# Output_Transceivers.net
KiCad netlist of a schematic drawn in Altium Designer
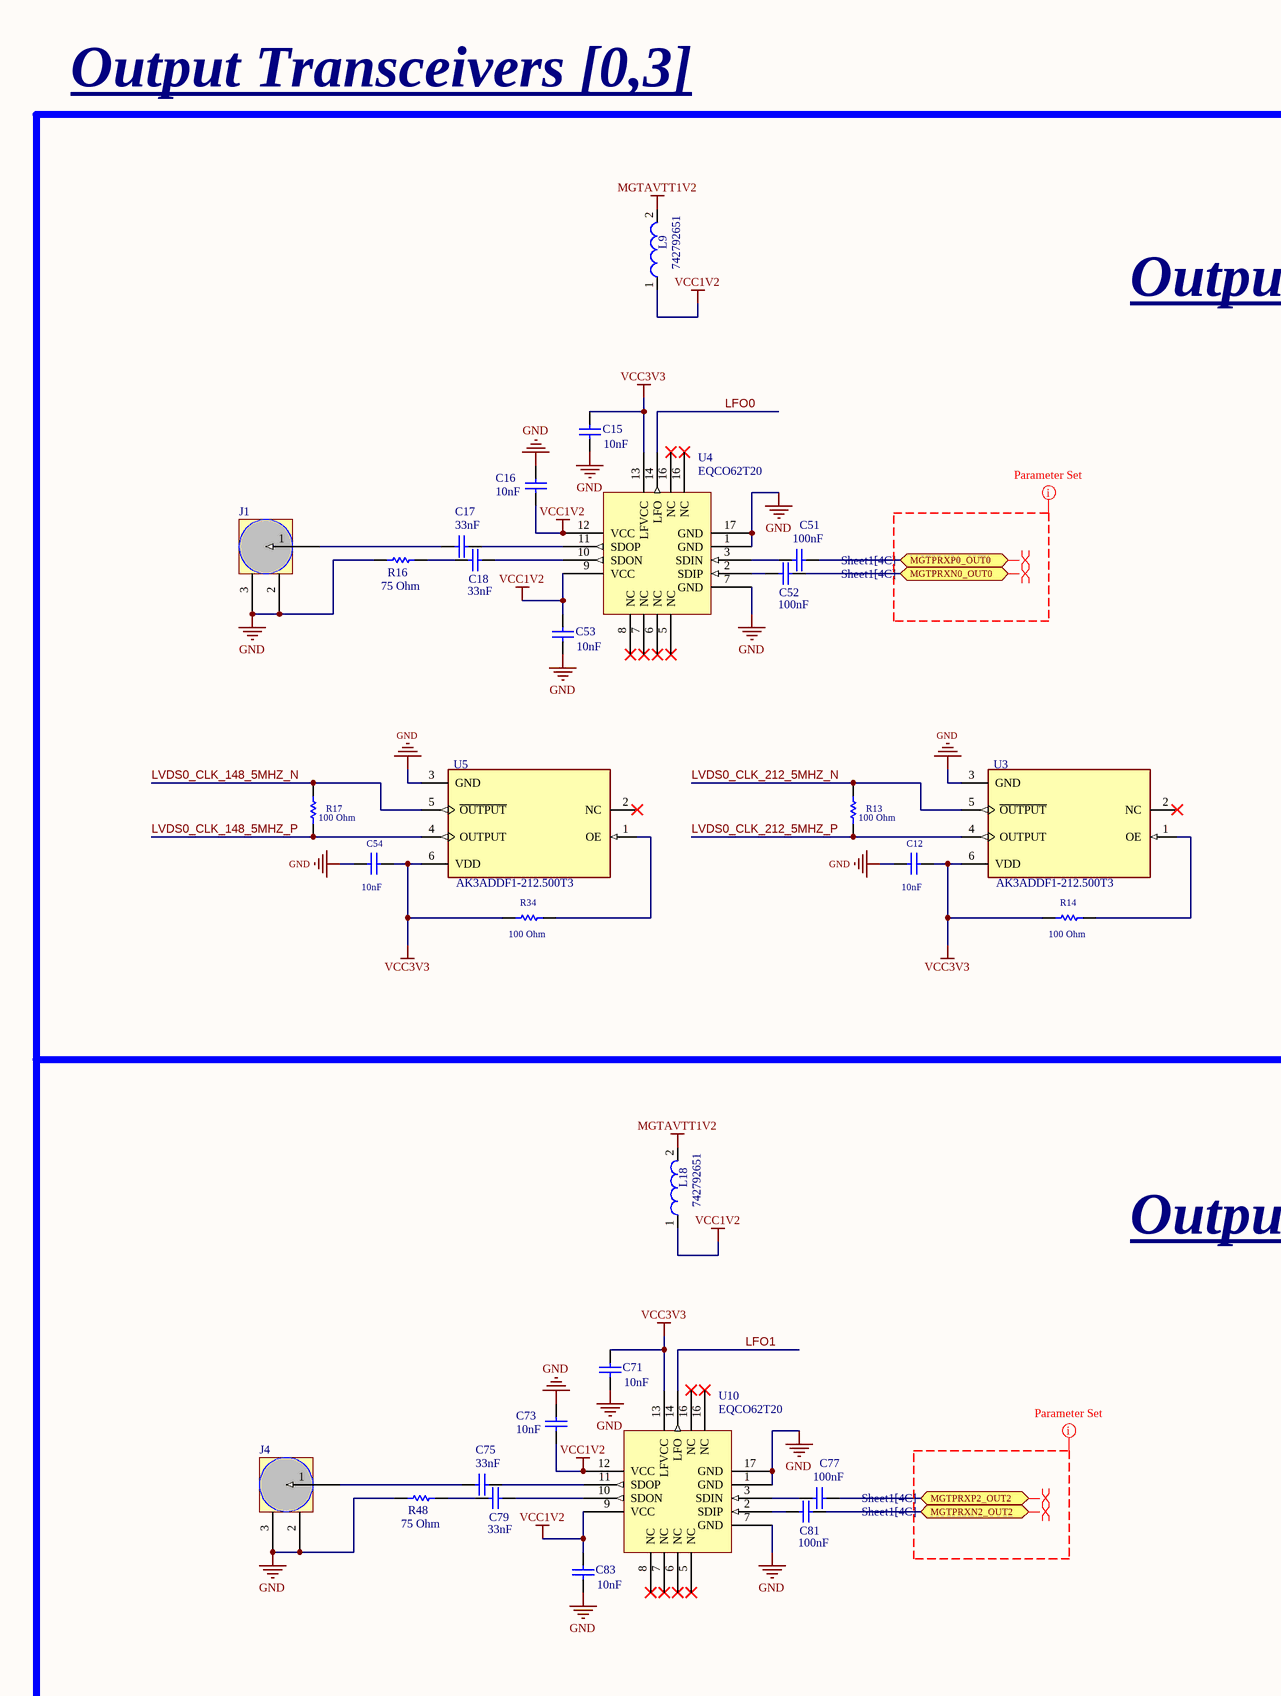
[diagram p0: Output Transceivers.SchDoc, left]
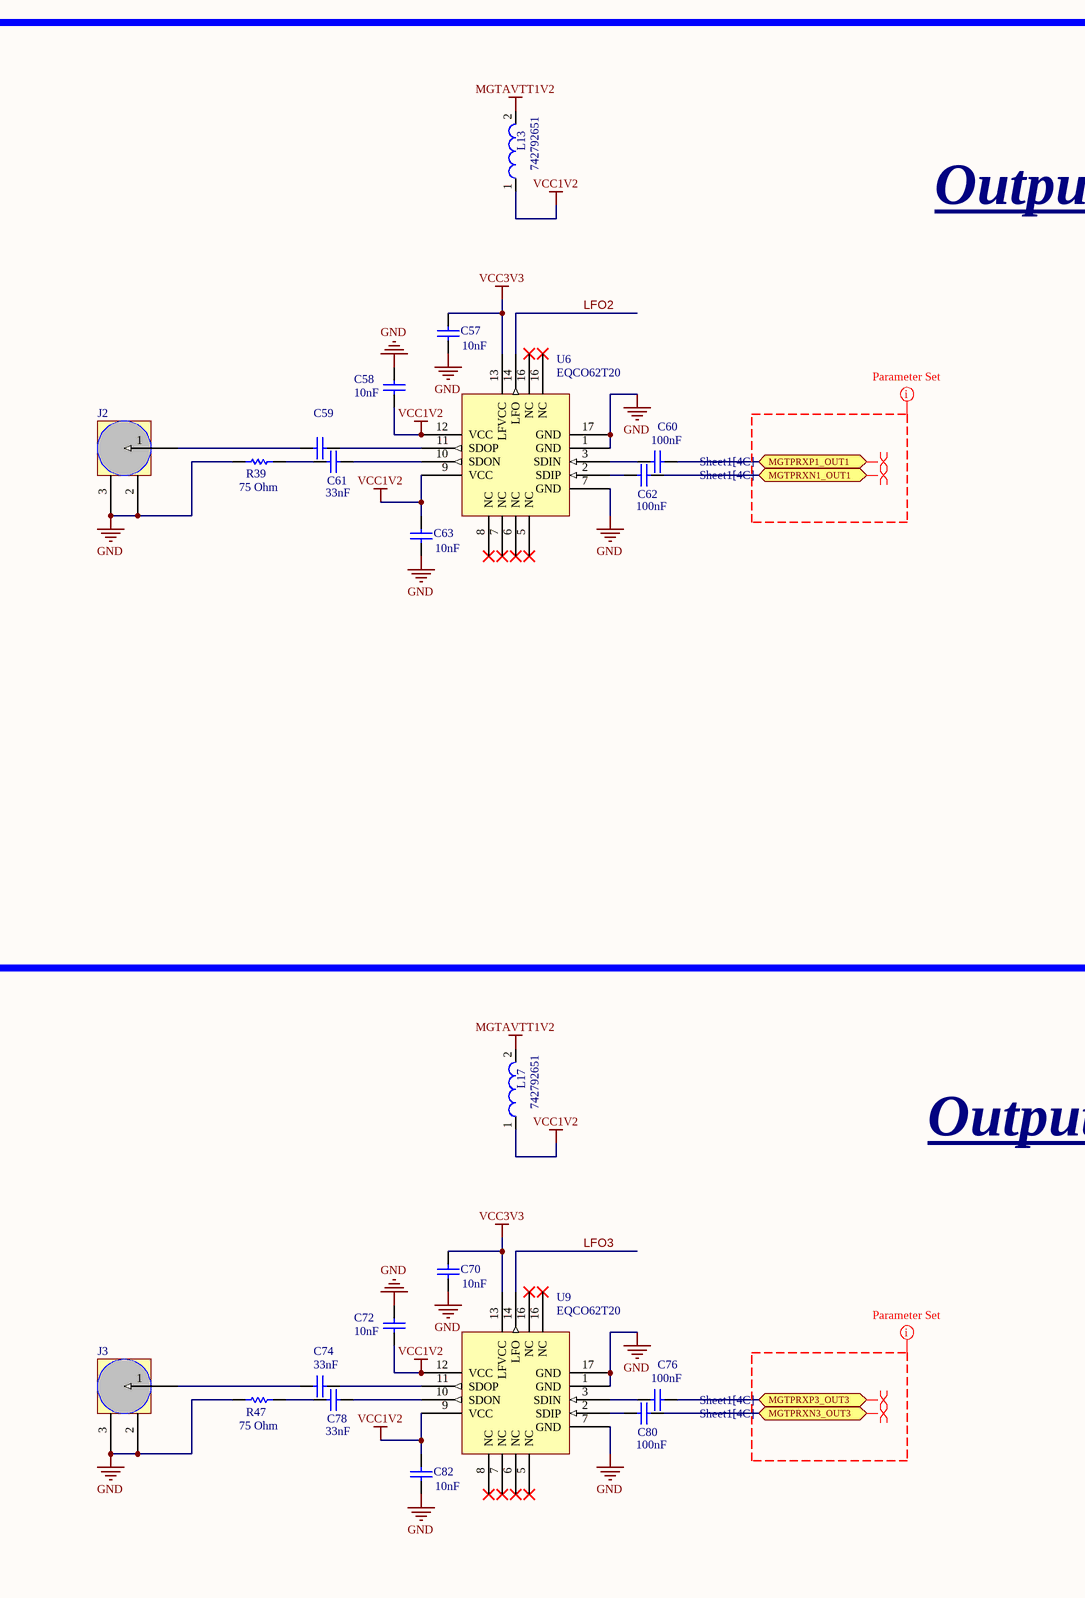
[diagram p1: Output Transceivers.SchDoc, right]

(export (version "E")
  (design (tool "Eeschema 10.0.6"))
  (components
    (comp (ref "C12")
      (value "10nF")
      (footprint "0402")
      (description "C0402C103K9RACTU 10nF 6.3V")
      (fields (field (name "PUBLISHER") "Altium Limited"))
      (libsource (lib "Camera_PCB_proj") (part "C0402"))
    )
    (comp (ref "C15")
      (value "10nF")
      (footprint "PCB_Display_Doru:0402")
      (description "C0402C103K9RACTU 10nF 6.3V")
      (fields (field (name "PUBLISHER") "Altium Limited"))
      (libsource (lib "Camera_PCB_proj") (part "C0402"))
    )
    (comp (ref "C16")
      (value "10nF")
      (footprint "PCB_Display_Doru:0402")
      (description "C0402C103K9RACTU 10nF 6.3V")
      (fields (field (name "PUBLISHER") "Altium Limited"))
      (libsource (lib "Camera_PCB_proj") (part "C0402"))
    )
    (comp (ref "C17")
      (value "33nF")
      (footprint "PCB_Display_Doru:0603")
      (description "C0603C333K5RACTU 33nF 50V")
      (fields (field (name "PUBLISHER") "Altium Limited"))
      (libsource (lib "Camera_PCB_proj") (part "C0603"))
    )
    (comp (ref "C18")
      (value "33nF")
      (footprint "PCB_Display_Doru:0603")
      (description "C0603C333K5RACTU 33nF 50V")
      (fields (field (name "PUBLISHER") "Altium Limited"))
      (libsource (lib "Camera_PCB_proj") (part "C0603"))
    )
    (comp (ref "C51")
      (value "100nF")
      (footprint "0402")
      (description "C0402C104K8RACTU 100nF 10V")
      (fields (field (name "PUBLISHER") "Altium Limited"))
      (libsource (lib "Camera_PCB_proj") (part "C0402"))
    )
    (comp (ref "C52")
      (value "100nF")
      (footprint "0402")
      (description "C0402C104K8RACTU 100nF 10V")
      (fields (field (name "PUBLISHER") "Altium Limited"))
      (libsource (lib "Camera_PCB_proj") (part "C0402"))
    )
    (comp (ref "C53")
      (value "10nF")
      (footprint "0402")
      (description "C0402C103K9RACTU 10nF 6.3V")
      (fields (field (name "PUBLISHER") "Altium Limited"))
      (libsource (lib "Camera_PCB_proj") (part "C0402"))
    )
    (comp (ref "C54")
      (value "10nF")
      (footprint "0402")
      (description "C0402C103K9RACTU 10nF 6.3V")
      (fields (field (name "PUBLISHER") "Altium Limited"))
      (libsource (lib "Camera_PCB_proj") (part "C0402"))
    )
    (comp (ref "C57")
      (value "10nF")
      (footprint "PCB_Display_Doru:0402")
      (description "C0402C103K9RACTU 10nF 6.3V")
      (fields (field (name "PUBLISHER") "Altium Limited"))
      (libsource (lib "Camera_PCB_proj") (part "C0402"))
    )
    (comp (ref "C58")
      (value "10nF")
      (footprint "PCB_Display_Doru:0402")
      (description "C0402C103K9RACTU 10nF 6.3V")
      (fields (field (name "PUBLISHER") "Altium Limited"))
      (libsource (lib "Camera_PCB_proj") (part "C0402"))
    )
    (comp (ref "C59")
      (value "33nF")
      (footprint "PCB_Display_Doru:0603")
      (description "C0603C333K5RACTU 33nF 50V")
      (fields (field (name "PUBLISHER") "Altium Limited"))
      (libsource (lib "Camera_PCB_proj") (part "C0603"))
    )
    (comp (ref "C60")
      (value "100nF")
      (footprint "0402")
      (description "C0402C104K8RACTU 100nF 10V")
      (fields (field (name "PUBLISHER") "Altium Limited"))
      (libsource (lib "Camera_PCB_proj") (part "C0402"))
    )
    (comp (ref "C61")
      (value "33nF")
      (footprint "PCB_Display_Doru:0603")
      (description "C0603C333K5RACTU 33nF 50V")
      (fields (field (name "PUBLISHER") "Altium Limited"))
      (libsource (lib "Camera_PCB_proj") (part "C0603"))
    )
    (comp (ref "C62")
      (value "100nF")
      (footprint "0402")
      (description "C0402C104K8RACTU 100nF 10V")
      (fields (field (name "PUBLISHER") "Altium Limited"))
      (libsource (lib "Camera_PCB_proj") (part "C0402"))
    )
    (comp (ref "C63")
      (value "10nF")
      (footprint "0402")
      (description "C0402C103K9RACTU 10nF 6.3V")
      (fields (field (name "PUBLISHER") "Altium Limited"))
      (libsource (lib "Camera_PCB_proj") (part "C0402"))
    )
    (comp (ref "C70")
      (value "10nF")
      (footprint "PCB_Display_Doru:0402")
      (description "C0402C103K9RACTU 10nF 6.3V")
      (fields (field (name "PUBLISHER") "Altium Limited"))
      (libsource (lib "Camera_PCB_proj") (part "C0402"))
    )
    (comp (ref "C71")
      (value "10nF")
      (footprint "PCB_Display_Doru:0402")
      (description "C0402C103K9RACTU 10nF 6.3V")
      (fields (field (name "PUBLISHER") "Altium Limited"))
      (libsource (lib "Camera_PCB_proj") (part "C0402"))
    )
    (comp (ref "C72")
      (value "10nF")
      (footprint "PCB_Display_Doru:0402")
      (description "C0402C103K9RACTU 10nF 6.3V")
      (fields (field (name "PUBLISHER") "Altium Limited"))
      (libsource (lib "Camera_PCB_proj") (part "C0402"))
    )
    (comp (ref "C73")
      (value "10nF")
      (footprint "PCB_Display_Doru:0402")
      (description "C0402C103K9RACTU 10nF 6.3V")
      (fields (field (name "PUBLISHER") "Altium Limited"))
      (libsource (lib "Camera_PCB_proj") (part "C0402"))
    )
    (comp (ref "C74")
      (value "33nF")
      (footprint "PCB_Display_Doru:0603")
      (description "C0603C333K5RACTU 33nF 50V")
      (fields (field (name "PUBLISHER") "Altium Limited"))
      (libsource (lib "Camera_PCB_proj") (part "C0603"))
    )
    (comp (ref "C75")
      (value "33nF")
      (footprint "PCB_Display_Doru:0603")
      (description "C0603C333K5RACTU 33nF 50V")
      (fields (field (name "PUBLISHER") "Altium Limited"))
      (libsource (lib "Camera_PCB_proj") (part "C0603"))
    )
    (comp (ref "C76")
      (value "100nF")
      (footprint "0402")
      (description "C0402C104K8RACTU 100nF 10V")
      (fields (field (name "PUBLISHER") "Altium Limited"))
      (libsource (lib "Camera_PCB_proj") (part "C0402"))
    )
    (comp (ref "C77")
      (value "100nF")
      (footprint "0402")
      (description "C0402C104K8RACTU 100nF 10V")
      (fields (field (name "PUBLISHER") "Altium Limited"))
      (libsource (lib "Camera_PCB_proj") (part "C0402"))
    )
    (comp (ref "C78")
      (value "33nF")
      (footprint "PCB_Display_Doru:0603")
      (description "C0603C333K5RACTU 33nF 50V")
      (fields (field (name "PUBLISHER") "Altium Limited"))
      (libsource (lib "Camera_PCB_proj") (part "C0603"))
    )
    (comp (ref "C79")
      (value "33nF")
      (footprint "PCB_Display_Doru:0603")
      (description "C0603C333K5RACTU 33nF 50V")
      (fields (field (name "PUBLISHER") "Altium Limited"))
      (libsource (lib "Camera_PCB_proj") (part "C0603"))
    )
    (comp (ref "C80")
      (value "100nF")
      (footprint "0402")
      (description "C0402C104K8RACTU 100nF 10V")
      (fields (field (name "PUBLISHER") "Altium Limited"))
      (libsource (lib "Camera_PCB_proj") (part "C0402"))
    )
    (comp (ref "C81")
      (value "100nF")
      (footprint "0402")
      (description "C0402C104K8RACTU 100nF 10V")
      (fields (field (name "PUBLISHER") "Altium Limited"))
      (libsource (lib "Camera_PCB_proj") (part "C0402"))
    )
    (comp (ref "C82")
      (value "10nF")
      (footprint "0402")
      (description "C0402C103K9RACTU 10nF 6.3V")
      (fields (field (name "PUBLISHER") "Altium Limited"))
      (libsource (lib "Camera_PCB_proj") (part "C0402"))
    )
    (comp (ref "C83")
      (value "10nF")
      (footprint "0402")
      (description "C0402C103K9RACTU 10nF 6.3V")
      (fields (field (name "PUBLISHER") "Altium Limited"))
      (libsource (lib "Camera_PCB_proj") (part "C0402"))
    )
    (comp (ref "J1")
      (value "~")
      (footprint "PCB_Display_Doru:PCBComponent_1 - duplicate")
      (description "Amphenol_BNC_HD_034_1018")
      (libsource (lib "") (part "Component_1_1"))
    )
    (comp (ref "J2")
      (value "~")
      (footprint "PCB_Display_Doru:PCBComponent_1 - duplicate")
      (description "Amphenol_BNC_HD_034_1018")
      (libsource (lib "") (part "Component_1_1"))
    )
    (comp (ref "J3")
      (value "~")
      (footprint "PCB_Display_Doru:PCBComponent_1 - duplicate")
      (description "Amphenol_BNC_HD_034_1018")
      (libsource (lib "") (part "Component_1_1"))
    )
    (comp (ref "J4")
      (value "~")
      (footprint "PCB_Display_Doru:PCBComponent_1 - duplicate")
      (description "Amphenol_BNC_HD_034_1018")
      (libsource (lib "") (part "Component_1_1"))
    )
    (comp (ref "L9")
      (value "742792651")
      (footprint "PCB_Display_Doru:SMD-0603")
      (description "SMD EMI Suppression Ferrite Bead WE-CBF, Z = 600 Ohm")
      (libsource (lib "Camera_PCB_proj") (part "742792651"))
    )
    (comp (ref "L13")
      (value "742792651")
      (footprint "PCB_Display_Doru:SMD-0603")
      (description "SMD EMI Suppression Ferrite Bead WE-CBF, Z = 600 Ohm")
      (libsource (lib "Camera_PCB_proj") (part "742792651"))
    )
    (comp (ref "L17")
      (value "742792651")
      (footprint "PCB_Display_Doru:SMD-0603")
      (description "SMD EMI Suppression Ferrite Bead WE-CBF, Z = 600 Ohm")
      (libsource (lib "Camera_PCB_proj") (part "742792651"))
    )
    (comp (ref "L18")
      (value "742792651")
      (footprint "PCB_Display_Doru:SMD-0603")
      (description "SMD EMI Suppression Ferrite Bead WE-CBF, Z = 600 Ohm")
      (libsource (lib "Camera_PCB_proj") (part "742792651"))
    )
    (comp (ref "R13")
      (value "100 Ohm")
      (footprint "PCB_Display_Doru:3-0603")
      (fields (field (name "PUBLISHER") "Altium Limited"))
      (libsource (lib "Camera_PCB_proj") (part "ERJ3EK"))
    )
    (comp (ref "R14")
      (value "100 Ohm")
      (footprint "PCB_Display_Doru:3-0603")
      (fields (field (name "PUBLISHER") "Altium Limited"))
      (libsource (lib "Camera_PCB_proj") (part "ERJ3EK"))
    )
    (comp (ref "R16")
      (value "75 Ohm")
      (footprint "PCB_Display_Doru:3-0603")
      (fields (field (name "PUBLISHER") "Altium Limited"))
      (libsource (lib "Camera_PCB_proj") (part "ERJ3EK"))
    )
    (comp (ref "R17")
      (value "100 Ohm")
      (footprint "PCB_Display_Doru:3-0603")
      (fields (field (name "PUBLISHER") "Altium Limited"))
      (libsource (lib "Camera_PCB_proj") (part "ERJ3EK"))
    )
    (comp (ref "R34")
      (value "100 Ohm")
      (footprint "PCB_Display_Doru:3-0603")
      (fields (field (name "PUBLISHER") "Altium Limited"))
      (libsource (lib "Camera_PCB_proj") (part "ERJ3EK"))
    )
    (comp (ref "R39")
      (value "75 Ohm")
      (footprint "PCB_Display_Doru:3-0603")
      (fields (field (name "PUBLISHER") "Altium Limited"))
      (libsource (lib "Camera_PCB_proj") (part "ERJ3EK"))
    )
    (comp (ref "R47")
      (value "75 Ohm")
      (footprint "PCB_Display_Doru:3-0603")
      (fields (field (name "PUBLISHER") "Altium Limited"))
      (libsource (lib "Camera_PCB_proj") (part "ERJ3EK"))
    )
    (comp (ref "R48")
      (value "75 Ohm")
      (footprint "PCB_Display_Doru:3-0603")
      (fields (field (name "PUBLISHER") "Altium Limited"))
      (libsource (lib "Camera_PCB_proj") (part "ERJ3EK"))
    )
    (comp (ref "U3")
      (value "AK3ADDF1-212.500T3")
      (footprint "PCB_Display_Doru:AX3DAF1-148.5000T")
      (description "148.5 MHz XO (Standard) LVDS Oscillator 3.3V Enable/Disable 6-SMD, No Lead")
      (fields (field (name "PART_NUMBER") "J00001"))
      (libsource (lib "Camera_PCB_proj") (part "AX3DAF1-148.5000T"))
    )
    (comp (ref "U4")
      (value "EQCO62T20")
      (footprint "PCB_Display_Doru:PCBComponent_1_2")
      (libsource (lib "Camera_PCB_proj") (part "Component_1"))
    )
    (comp (ref "U5")
      (value "AK3ADDF1-212.500T3")
      (footprint "PCB_Display_Doru:AX3DAF1-148.5000T")
      (description "148.5 MHz XO (Standard) LVDS Oscillator 3.3V Enable/Disable 6-SMD, No Lead")
      (fields (field (name "PART_NUMBER") "J00001"))
      (libsource (lib "Camera_PCB_proj") (part "AX3DAF1-148.5000T"))
    )
    (comp (ref "U6")
      (value "EQCO62T20")
      (footprint "PCB_Display_Doru:PCBComponent_1_2")
      (libsource (lib "Camera_PCB_proj") (part "Component_1"))
    )
    (comp (ref "U9")
      (value "EQCO62T20")
      (footprint "PCB_Display_Doru:PCBComponent_1_2")
      (libsource (lib "Camera_PCB_proj") (part "Component_1"))
    )
    (comp (ref "U10")
      (value "EQCO62T20")
      (footprint "PCB_Display_Doru:PCBComponent_1_2")
      (libsource (lib "Camera_PCB_proj") (part "Component_1"))
    )
  )
  (nets
    (net (code "1") (name "/LFO0") (class "Default")
      (node (ref "U4") (pin "14") (pinfunction "LFO_14") (pintype "output"))
    )
    (net (code "2") (name "/LFO1") (class "Default")
      (node (ref "U10") (pin "14") (pinfunction "LFO_14") (pintype "output"))
    )
    (net (code "3") (name "/LFO2") (class "Default")
      (node (ref "U6") (pin "14") (pinfunction "LFO_14") (pintype "output"))
    )
    (net (code "4") (name "/LFO3") (class "Default")
      (node (ref "U9") (pin "14") (pinfunction "LFO_14") (pintype "output"))
    )
    (net (code "5") (name "/LVDS0_CLK_148_5MHZ_N") (class "Default")
      (node (ref "R17") (pin "2") (pinfunction "2_2") (pintype "passive"))
      (node (ref "U5") (pin "5") (pinfunction "~{OUTPUT}_5") (pintype "output"))
    )
    (net (code "6") (name "/LVDS0_CLK_148_5MHZ_P") (class "Default")
      (node (ref "R17") (pin "1") (pinfunction "1_1") (pintype "passive"))
      (node (ref "U5") (pin "4") (pinfunction "OUTPUT_4") (pintype "output"))
    )
    (net (code "7") (name "/LVDS0_CLK_212_5MHZ_N") (class "Default")
      (node (ref "R13") (pin "2") (pinfunction "2_2") (pintype "passive"))
      (node (ref "U3") (pin "5") (pinfunction "~{OUTPUT}_5") (pintype "output"))
    )
    (net (code "8") (name "/LVDS0_CLK_212_5MHZ_P") (class "Default")
      (node (ref "R13") (pin "1") (pinfunction "1_1") (pintype "passive"))
      (node (ref "U3") (pin "4") (pinfunction "OUTPUT_4") (pintype "output"))
    )
    (net (code "9") (name "/MGTPRXN0_OUT0") (class "Default")
      (node (ref "C52") (pin "2") (pinfunction "2_2") (pintype "passive"))
    )
    (net (code "10") (name "/MGTPRXN1_OUT1") (class "Default")
      (node (ref "C62") (pin "2") (pinfunction "2_2") (pintype "passive"))
    )
    (net (code "11") (name "/MGTPRXN2_OUT2") (class "Default")
      (node (ref "C81") (pin "2") (pinfunction "2_2") (pintype "passive"))
    )
    (net (code "12") (name "/MGTPRXN3_OUT3") (class "Default")
      (node (ref "C80") (pin "2") (pinfunction "2_2") (pintype "passive"))
    )
    (net (code "13") (name "/MGTPRXP0_OUT0") (class "Default")
      (node (ref "C51") (pin "2") (pinfunction "2_2") (pintype "passive"))
    )
    (net (code "14") (name "/MGTPRXP1_OUT1") (class "Default")
      (node (ref "C60") (pin "2") (pinfunction "2_2") (pintype "passive"))
    )
    (net (code "15") (name "/MGTPRXP2_OUT2") (class "Default")
      (node (ref "C77") (pin "2") (pinfunction "2_2") (pintype "passive"))
    )
    (net (code "16") (name "/MGTPRXP3_OUT3") (class "Default")
      (node (ref "C76") (pin "2") (pinfunction "2_2") (pintype "passive"))
    )
    (net (code "17") (name "GND") (class "Default")
      (node (ref "C12") (pin "1") (pinfunction "1_1") (pintype "passive"))
      (node (ref "C15") (pin "1") (pinfunction "1_1") (pintype "passive"))
      (node (ref "C16") (pin "2") (pinfunction "2_2") (pintype "passive"))
      (node (ref "C53") (pin "1") (pinfunction "1_1") (pintype "passive"))
      (node (ref "C54") (pin "1") (pinfunction "1_1") (pintype "passive"))
      (node (ref "C57") (pin "1") (pinfunction "1_1") (pintype "passive"))
      (node (ref "C58") (pin "2") (pinfunction "2_2") (pintype "passive"))
      (node (ref "C63") (pin "1") (pinfunction "1_1") (pintype "passive"))
      (node (ref "C70") (pin "1") (pinfunction "1_1") (pintype "passive"))
      (node (ref "C71") (pin "1") (pinfunction "1_1") (pintype "passive"))
      (node (ref "C72") (pin "2") (pinfunction "2_2") (pintype "passive"))
      (node (ref "C73") (pin "2") (pinfunction "2_2") (pintype "passive"))
      (node (ref "C82") (pin "1") (pinfunction "1_1") (pintype "passive"))
      (node (ref "C83") (pin "1") (pinfunction "1_1") (pintype "passive"))
      (node (ref "J1") (pin "2") (pintype "passive"))
      (node (ref "J1") (pin "3") (pintype "passive"))
      (node (ref "J2") (pin "2") (pintype "passive"))
      (node (ref "J2") (pin "3") (pintype "passive"))
      (node (ref "J3") (pin "2") (pintype "passive"))
      (node (ref "J3") (pin "3") (pintype "passive"))
      (node (ref "J4") (pin "2") (pintype "passive"))
      (node (ref "J4") (pin "3") (pintype "passive"))
      (node (ref "R16") (pin "1") (pinfunction "1_1") (pintype "passive"))
      (node (ref "R39") (pin "1") (pinfunction "1_1") (pintype "passive"))
      (node (ref "R47") (pin "1") (pinfunction "1_1") (pintype "passive"))
      (node (ref "R48") (pin "1") (pinfunction "1_1") (pintype "passive"))
      (node (ref "U10") (pin "1") (pinfunction "GND_1") (pintype "power_in"))
      (node (ref "U10") (pin "17") (pinfunction "GND_17") (pintype "power_in"))
      (node (ref "U10") (pin "7") (pinfunction "GND_7") (pintype "power_in"))
      (node (ref "U3") (pin "3") (pinfunction "GND_3") (pintype "power_in"))
      (node (ref "U4") (pin "1") (pinfunction "GND_1") (pintype "power_in"))
      (node (ref "U4") (pin "17") (pinfunction "GND_17") (pintype "power_in"))
      (node (ref "U4") (pin "7") (pinfunction "GND_7") (pintype "power_in"))
      (node (ref "U5") (pin "3") (pinfunction "GND_3") (pintype "power_in"))
      (node (ref "U6") (pin "1") (pinfunction "GND_1") (pintype "power_in"))
      (node (ref "U6") (pin "17") (pinfunction "GND_17") (pintype "power_in"))
      (node (ref "U6") (pin "7") (pinfunction "GND_7") (pintype "power_in"))
      (node (ref "U9") (pin "1") (pinfunction "GND_1") (pintype "power_in"))
      (node (ref "U9") (pin "17") (pinfunction "GND_17") (pintype "power_in"))
      (node (ref "U9") (pin "7") (pinfunction "GND_7") (pintype "power_in"))
    )
    (net (code "18") (name "MGTAVTT1V2") (class "Default")
      (node (ref "L13") (pin "2") (pinfunction "2_2") (pintype "passive"))
      (node (ref "L17") (pin "2") (pinfunction "2_2") (pintype "passive"))
      (node (ref "L18") (pin "2") (pinfunction "2_2") (pintype "passive"))
      (node (ref "L9") (pin "2") (pinfunction "2_2") (pintype "passive"))
    )
    (net (code "19") (name "Net-(C17-Pad1)") (class "Default")
      (node (ref "C17") (pin "1") (pinfunction "1_1") (pintype "passive"))
      (node (ref "J1") (pin "1") (pintype "input"))
    )
    (net (code "20") (name "Net-(C18-Pad1)") (class "Default")
      (node (ref "C18") (pin "1") (pinfunction "1_1") (pintype "passive"))
      (node (ref "R16") (pin "2") (pinfunction "2_2") (pintype "passive"))
    )
    (net (code "21") (name "Net-(C59-Pad1)") (class "Default")
      (node (ref "C59") (pin "1") (pinfunction "1_1") (pintype "passive"))
      (node (ref "J2") (pin "1") (pintype "input"))
    )
    (net (code "22") (name "Net-(C61-Pad1)") (class "Default")
      (node (ref "C61") (pin "1") (pinfunction "1_1") (pintype "passive"))
      (node (ref "R39") (pin "2") (pinfunction "2_2") (pintype "passive"))
    )
    (net (code "23") (name "Net-(C74-Pad1)") (class "Default")
      (node (ref "C74") (pin "1") (pinfunction "1_1") (pintype "passive"))
      (node (ref "J3") (pin "1") (pintype "input"))
    )
    (net (code "24") (name "Net-(C75-Pad1)") (class "Default")
      (node (ref "C75") (pin "1") (pinfunction "1_1") (pintype "passive"))
      (node (ref "J4") (pin "1") (pintype "input"))
    )
    (net (code "25") (name "Net-(C78-Pad1)") (class "Default")
      (node (ref "C78") (pin "1") (pinfunction "1_1") (pintype "passive"))
      (node (ref "R47") (pin "2") (pinfunction "2_2") (pintype "passive"))
    )
    (net (code "26") (name "Net-(C79-Pad1)") (class "Default")
      (node (ref "C79") (pin "1") (pinfunction "1_1") (pintype "passive"))
      (node (ref "R48") (pin "2") (pinfunction "2_2") (pintype "passive"))
    )
    (net (code "27") (name "Net-(U3-OE)") (class "Default")
      (node (ref "R14") (pin "2") (pinfunction "2_2") (pintype "passive"))
      (node (ref "U3") (pin "1") (pinfunction "OE_1") (pintype "input"))
    )
    (net (code "28") (name "Net-(U4-SDIN)") (class "Default")
      (node (ref "C51") (pin "1") (pinfunction "1_1") (pintype "passive"))
      (node (ref "U4") (pin "3") (pinfunction "SDIN_3") (pintype "input"))
    )
    (net (code "29") (name "Net-(U4-SDIP)") (class "Default")
      (node (ref "C52") (pin "1") (pinfunction "1_1") (pintype "passive"))
      (node (ref "U4") (pin "2") (pinfunction "SDIP_2") (pintype "input"))
    )
    (net (code "30") (name "Net-(U4-SDON)") (class "Default")
      (node (ref "C18") (pin "2") (pinfunction "2_2") (pintype "passive"))
      (node (ref "U4") (pin "10") (pinfunction "SDON_10") (pintype "output"))
    )
    (net (code "31") (name "Net-(U4-SDOP)") (class "Default")
      (node (ref "C17") (pin "2") (pinfunction "2_2") (pintype "passive"))
      (node (ref "U4") (pin "11") (pinfunction "SDOP_11") (pintype "output"))
    )
    (net (code "32") (name "Net-(U5-OE)") (class "Default")
      (node (ref "R34") (pin "2") (pinfunction "2_2") (pintype "passive"))
      (node (ref "U5") (pin "1") (pinfunction "OE_1") (pintype "input"))
    )
    (net (code "33") (name "Net-(U6-SDIN)") (class "Default")
      (node (ref "C60") (pin "1") (pinfunction "1_1") (pintype "passive"))
      (node (ref "U6") (pin "3") (pinfunction "SDIN_3") (pintype "input"))
    )
    (net (code "34") (name "Net-(U6-SDIP)") (class "Default")
      (node (ref "C62") (pin "1") (pinfunction "1_1") (pintype "passive"))
      (node (ref "U6") (pin "2") (pinfunction "SDIP_2") (pintype "input"))
    )
    (net (code "35") (name "Net-(U6-SDON)") (class "Default")
      (node (ref "C61") (pin "2") (pinfunction "2_2") (pintype "passive"))
      (node (ref "U6") (pin "10") (pinfunction "SDON_10") (pintype "output"))
    )
    (net (code "36") (name "Net-(U6-SDOP)") (class "Default")
      (node (ref "C59") (pin "2") (pinfunction "2_2") (pintype "passive"))
      (node (ref "U6") (pin "11") (pinfunction "SDOP_11") (pintype "output"))
    )
    (net (code "37") (name "Net-(U9-SDIN)") (class "Default")
      (node (ref "C76") (pin "1") (pinfunction "1_1") (pintype "passive"))
      (node (ref "U9") (pin "3") (pinfunction "SDIN_3") (pintype "input"))
    )
    (net (code "38") (name "Net-(U9-SDIP)") (class "Default")
      (node (ref "C80") (pin "1") (pinfunction "1_1") (pintype "passive"))
      (node (ref "U9") (pin "2") (pinfunction "SDIP_2") (pintype "input"))
    )
    (net (code "39") (name "Net-(U9-SDON)") (class "Default")
      (node (ref "C78") (pin "2") (pinfunction "2_2") (pintype "passive"))
      (node (ref "U9") (pin "10") (pinfunction "SDON_10") (pintype "output"))
    )
    (net (code "40") (name "Net-(U9-SDOP)") (class "Default")
      (node (ref "C74") (pin "2") (pinfunction "2_2") (pintype "passive"))
      (node (ref "U9") (pin "11") (pinfunction "SDOP_11") (pintype "output"))
    )
    (net (code "41") (name "Net-(U10-SDIN)") (class "Default")
      (node (ref "C77") (pin "1") (pinfunction "1_1") (pintype "passive"))
      (node (ref "U10") (pin "3") (pinfunction "SDIN_3") (pintype "input"))
    )
    (net (code "42") (name "Net-(U10-SDIP)") (class "Default")
      (node (ref "C81") (pin "1") (pinfunction "1_1") (pintype "passive"))
      (node (ref "U10") (pin "2") (pinfunction "SDIP_2") (pintype "input"))
    )
    (net (code "43") (name "Net-(U10-SDON)") (class "Default")
      (node (ref "C79") (pin "2") (pinfunction "2_2") (pintype "passive"))
      (node (ref "U10") (pin "10") (pinfunction "SDON_10") (pintype "output"))
    )
    (net (code "44") (name "Net-(U10-SDOP)") (class "Default")
      (node (ref "C75") (pin "2") (pinfunction "2_2") (pintype "passive"))
      (node (ref "U10") (pin "11") (pinfunction "SDOP_11") (pintype "output"))
    )
    (net (code "45") (name "VCC1V2") (class "Default")
      (node (ref "C16") (pin "1") (pinfunction "1_1") (pintype "passive"))
      (node (ref "C53") (pin "2") (pinfunction "2_2") (pintype "passive"))
      (node (ref "C58") (pin "1") (pinfunction "1_1") (pintype "passive"))
      (node (ref "C63") (pin "2") (pinfunction "2_2") (pintype "passive"))
      (node (ref "C72") (pin "1") (pinfunction "1_1") (pintype "passive"))
      (node (ref "C73") (pin "1") (pinfunction "1_1") (pintype "passive"))
      (node (ref "C82") (pin "2") (pinfunction "2_2") (pintype "passive"))
      (node (ref "C83") (pin "2") (pinfunction "2_2") (pintype "passive"))
      (node (ref "L13") (pin "1") (pinfunction "1_1") (pintype "passive"))
      (node (ref "L17") (pin "1") (pinfunction "1_1") (pintype "passive"))
      (node (ref "L18") (pin "1") (pinfunction "1_1") (pintype "passive"))
      (node (ref "L9") (pin "1") (pinfunction "1_1") (pintype "passive"))
      (node (ref "U10") (pin "12") (pinfunction "VCC_12") (pintype "passive"))
      (node (ref "U10") (pin "9") (pinfunction "VCC_9") (pintype "passive"))
      (node (ref "U4") (pin "12") (pinfunction "VCC_12") (pintype "passive"))
      (node (ref "U4") (pin "9") (pinfunction "VCC_9") (pintype "passive"))
      (node (ref "U6") (pin "12") (pinfunction "VCC_12") (pintype "passive"))
      (node (ref "U6") (pin "9") (pinfunction "VCC_9") (pintype "passive"))
      (node (ref "U9") (pin "12") (pinfunction "VCC_12") (pintype "passive"))
      (node (ref "U9") (pin "9") (pinfunction "VCC_9") (pintype "passive"))
    )
    (net (code "46") (name "VCC3V3") (class "Default")
      (node (ref "C12") (pin "2") (pinfunction "2_2") (pintype "passive"))
      (node (ref "C15") (pin "2") (pinfunction "2_2") (pintype "passive"))
      (node (ref "C54") (pin "2") (pinfunction "2_2") (pintype "passive"))
      (node (ref "C57") (pin "2") (pinfunction "2_2") (pintype "passive"))
      (node (ref "C70") (pin "2") (pinfunction "2_2") (pintype "passive"))
      (node (ref "C71") (pin "2") (pinfunction "2_2") (pintype "passive"))
      (node (ref "R14") (pin "1") (pinfunction "1_1") (pintype "passive"))
      (node (ref "R34") (pin "1") (pinfunction "1_1") (pintype "passive"))
      (node (ref "U10") (pin "13") (pinfunction "LFVCC_13") (pintype "power_in"))
      (node (ref "U3") (pin "6") (pinfunction "VDD_6") (pintype "power_in"))
      (node (ref "U4") (pin "13") (pinfunction "LFVCC_13") (pintype "power_in"))
      (node (ref "U5") (pin "6") (pinfunction "VDD_6") (pintype "power_in"))
      (node (ref "U6") (pin "13") (pinfunction "LFVCC_13") (pintype "power_in"))
      (node (ref "U9") (pin "13") (pinfunction "LFVCC_13") (pintype "power_in"))
    )
    (net (code "47") (name "unconnected-(U3-NC-Pad2)") (class "Default")
      (node (ref "U3") (pin "2") (pinfunction "NC_2") (pintype "passive+no_connect"))
    )
    (net (code "48") (name "unconnected-(U4-NC-Pad5)") (class "Default")
      (node (ref "U4") (pin "5") (pinfunction "NC_5") (pintype "passive+no_connect"))
    )
    (net (code "49") (name "unconnected-(U4-NC-Pad6)") (class "Default")
      (node (ref "U4") (pin "6") (pinfunction "NC_6") (pintype "passive+no_connect"))
    )
    (net (code "50") (name "unconnected-(U4-NC-Pad7)") (class "Default")
      (node (ref "U4") (pin "7") (pinfunction "NC_7") (pintype "passive+no_connect"))
    )
    (net (code "51") (name "unconnected-(U4-NC-Pad8)") (class "Default")
      (node (ref "U4") (pin "8") (pinfunction "NC_8") (pintype "passive+no_connect"))
    )
    (net (code "52") (name "unconnected-(U4-NC-Pad16)") (class "Default")
      (node (ref "U4") (pin "16") (pinfunction "NC_16") (pintype "passive+no_connect"))
    )
    (net (code "53") (name "unconnected-(U4-NC-Pad16)_1") (class "Default")
      (node (ref "U4") (pin "16") (pinfunction "NC_16") (pintype "passive+no_connect"))
    )
    (net (code "54") (name "unconnected-(U5-NC-Pad2)") (class "Default")
      (node (ref "U5") (pin "2") (pinfunction "NC_2") (pintype "passive+no_connect"))
    )
    (net (code "55") (name "unconnected-(U6-NC-Pad5)") (class "Default")
      (node (ref "U6") (pin "5") (pinfunction "NC_5") (pintype "passive+no_connect"))
    )
    (net (code "56") (name "unconnected-(U6-NC-Pad6)") (class "Default")
      (node (ref "U6") (pin "6") (pinfunction "NC_6") (pintype "passive+no_connect"))
    )
    (net (code "57") (name "unconnected-(U6-NC-Pad7)") (class "Default")
      (node (ref "U6") (pin "7") (pinfunction "NC_7") (pintype "passive+no_connect"))
    )
    (net (code "58") (name "unconnected-(U6-NC-Pad8)") (class "Default")
      (node (ref "U6") (pin "8") (pinfunction "NC_8") (pintype "passive+no_connect"))
    )
    (net (code "59") (name "unconnected-(U6-NC-Pad16)") (class "Default")
      (node (ref "U6") (pin "16") (pinfunction "NC_16") (pintype "passive+no_connect"))
    )
    (net (code "60") (name "unconnected-(U6-NC-Pad16)_1") (class "Default")
      (node (ref "U6") (pin "16") (pinfunction "NC_16") (pintype "passive+no_connect"))
    )
    (net (code "61") (name "unconnected-(U9-NC-Pad5)") (class "Default")
      (node (ref "U9") (pin "5") (pinfunction "NC_5") (pintype "passive+no_connect"))
    )
    (net (code "62") (name "unconnected-(U9-NC-Pad6)") (class "Default")
      (node (ref "U9") (pin "6") (pinfunction "NC_6") (pintype "passive+no_connect"))
    )
    (net (code "63") (name "unconnected-(U9-NC-Pad7)") (class "Default")
      (node (ref "U9") (pin "7") (pinfunction "NC_7") (pintype "passive+no_connect"))
    )
    (net (code "64") (name "unconnected-(U9-NC-Pad8)") (class "Default")
      (node (ref "U9") (pin "8") (pinfunction "NC_8") (pintype "passive+no_connect"))
    )
    (net (code "65") (name "unconnected-(U9-NC-Pad16)") (class "Default")
      (node (ref "U9") (pin "16") (pinfunction "NC_16") (pintype "passive+no_connect"))
    )
    (net (code "66") (name "unconnected-(U9-NC-Pad16)_1") (class "Default")
      (node (ref "U9") (pin "16") (pinfunction "NC_16") (pintype "passive+no_connect"))
    )
    (net (code "67") (name "unconnected-(U10-NC-Pad5)") (class "Default")
      (node (ref "U10") (pin "5") (pinfunction "NC_5") (pintype "passive+no_connect"))
    )
    (net (code "68") (name "unconnected-(U10-NC-Pad6)") (class "Default")
      (node (ref "U10") (pin "6") (pinfunction "NC_6") (pintype "passive+no_connect"))
    )
    (net (code "69") (name "unconnected-(U10-NC-Pad7)") (class "Default")
      (node (ref "U10") (pin "7") (pinfunction "NC_7") (pintype "passive+no_connect"))
    )
    (net (code "70") (name "unconnected-(U10-NC-Pad8)") (class "Default")
      (node (ref "U10") (pin "8") (pinfunction "NC_8") (pintype "passive+no_connect"))
    )
    (net (code "71") (name "unconnected-(U10-NC-Pad16)") (class "Default")
      (node (ref "U10") (pin "16") (pinfunction "NC_16") (pintype "passive+no_connect"))
    )
    (net (code "72") (name "unconnected-(U10-NC-Pad16)_1") (class "Default")
      (node (ref "U10") (pin "16") (pinfunction "NC_16") (pintype "passive+no_connect"))
    )
  )
)
